# ArbPwrBoost_P6.net
KiCad netlist of a schematic drawn in Altium Designer
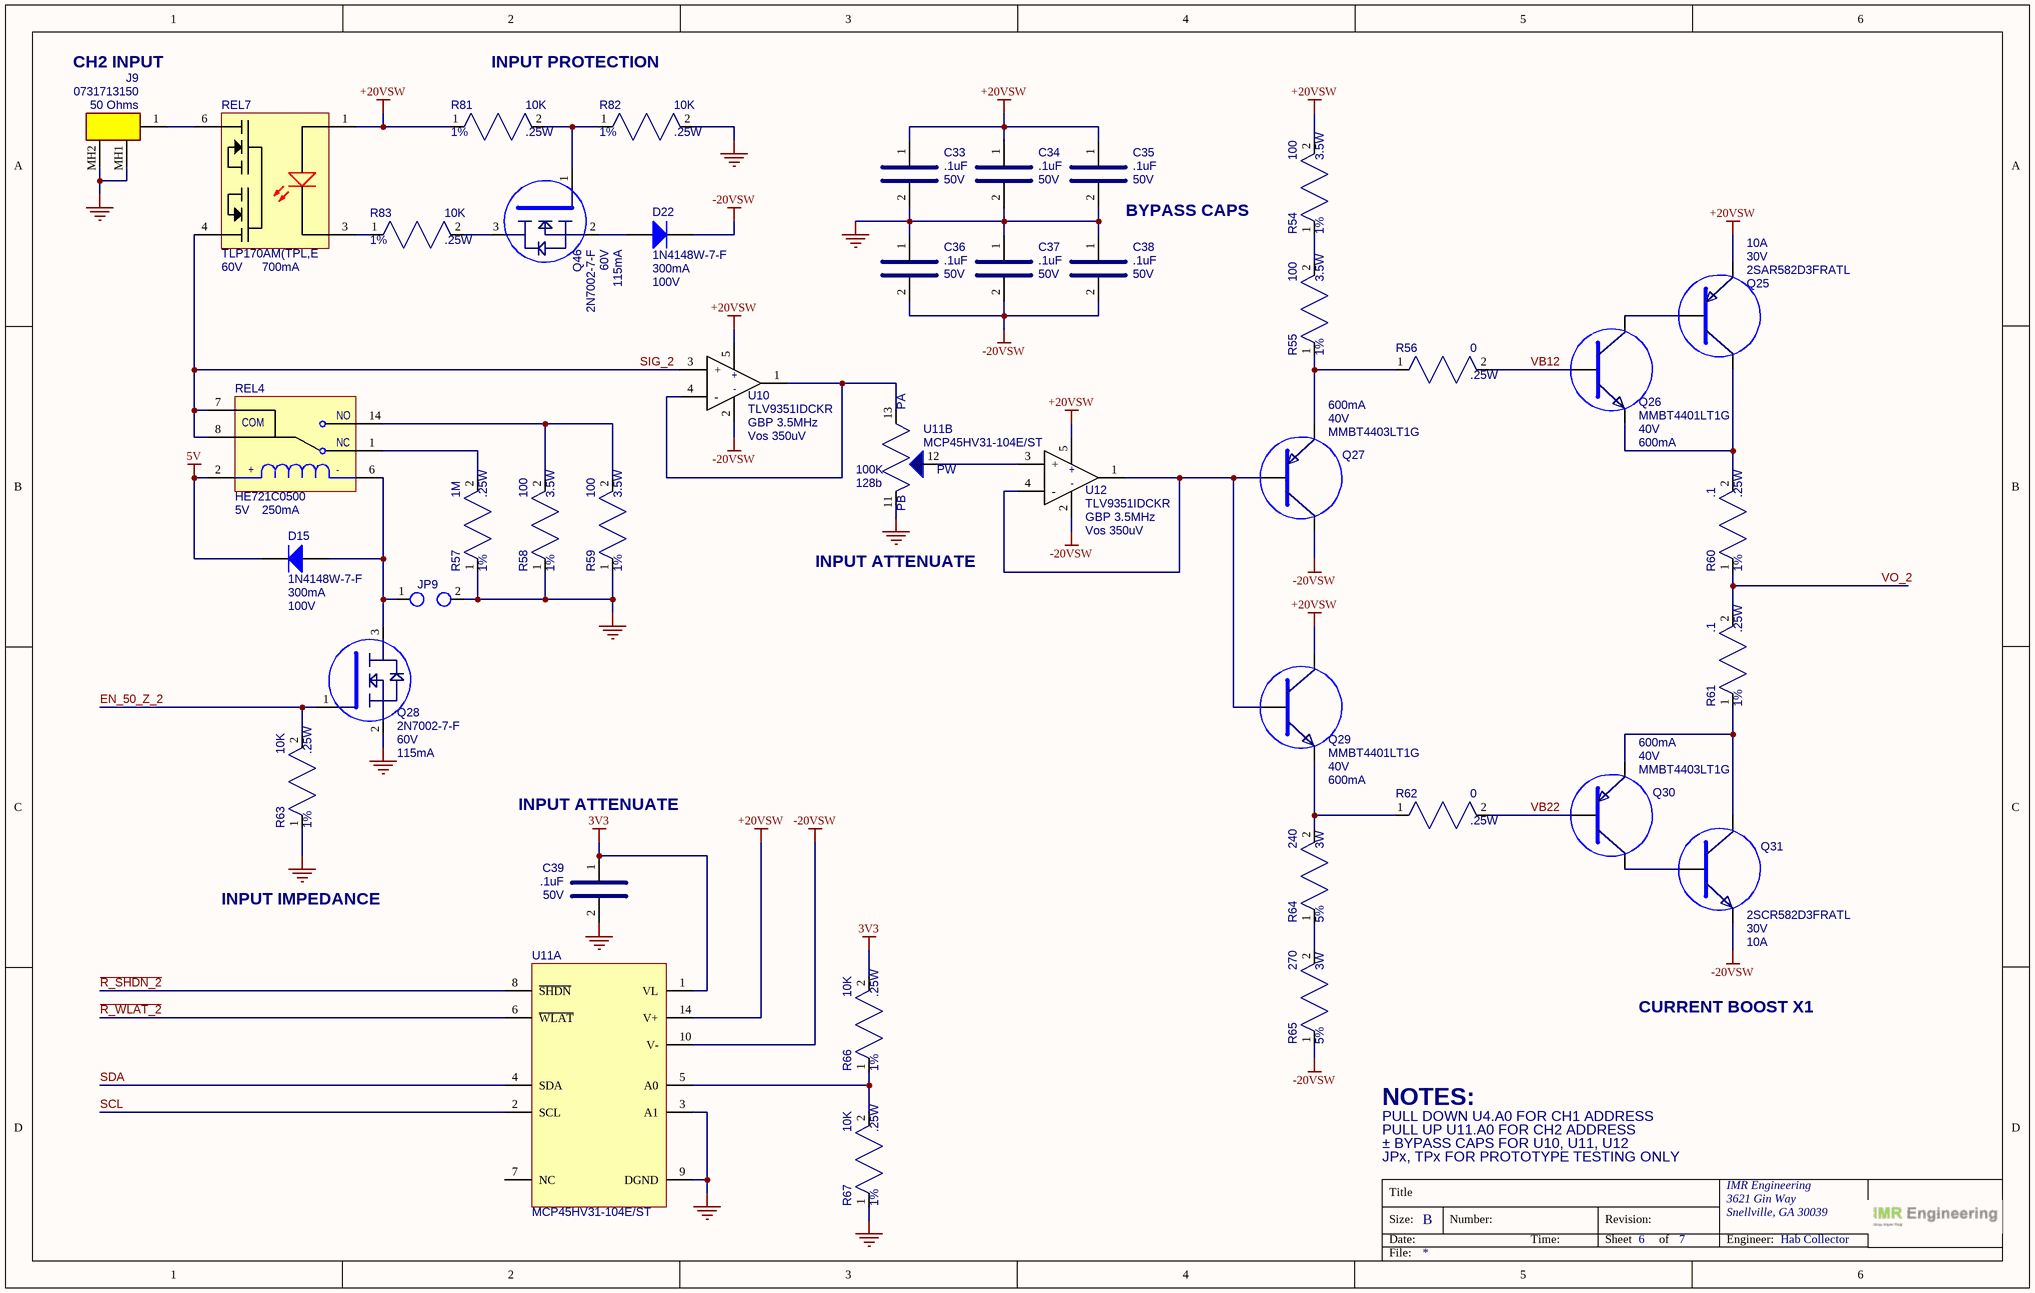
[diagram p0: ArbPwrBoost_P6.SchDoc]

(export (version "E")
  (design (tool "Eeschema 10.0.6"))
  (components
    (comp (ref "C33")
      (value ".1uF")
      (footprint "CAP_0805")
      (description "CAP CER 0.1UF 50V X7R 0805")
      (fields
        (field (name "MFG") "KYOCERA AVX")
        (field (name "VOLTAGE") "50V")
        (field (name "Comment") "KGM21NR71H104KT")
      )
      (libsource (lib "IMR_LIB_SCH_R2") (part "CAP_SMD_0.1UF_50V_0805"))
    )
    (comp (ref "C34")
      (value ".1uF")
      (footprint "CAP_0805")
      (description "CAP CER 0.1UF 50V X7R 0805")
      (fields
        (field (name "MFG") "KYOCERA AVX")
        (field (name "VOLTAGE") "50V")
        (field (name "Comment") "KGM21NR71H104KT")
      )
      (libsource (lib "IMR_LIB_SCH_R2") (part "CAP_SMD_0.1UF_50V_0805"))
    )
    (comp (ref "C35")
      (value ".1uF")
      (footprint "CAP_0805")
      (description "CAP CER 0.1UF 50V X7R 0805")
      (fields
        (field (name "MFG") "KYOCERA AVX")
        (field (name "VOLTAGE") "50V")
        (field (name "Comment") "KGM21NR71H104KT")
      )
      (libsource (lib "IMR_LIB_SCH_R2") (part "CAP_SMD_0.1UF_50V_0805"))
    )
    (comp (ref "C36")
      (value ".1uF")
      (footprint "CAP_0805")
      (description "CAP CER 0.1UF 50V X7R 0805")
      (fields
        (field (name "MFG") "KYOCERA AVX")
        (field (name "VOLTAGE") "50V")
        (field (name "Comment") "KGM21NR71H104KT")
      )
      (libsource (lib "IMR_LIB_SCH_R2") (part "CAP_SMD_0.1UF_50V_0805"))
    )
    (comp (ref "C37")
      (value ".1uF")
      (footprint "CAP_0805")
      (description "CAP CER 0.1UF 50V X7R 0805")
      (fields
        (field (name "MFG") "KYOCERA AVX")
        (field (name "VOLTAGE") "50V")
        (field (name "Comment") "KGM21NR71H104KT")
      )
      (libsource (lib "IMR_LIB_SCH_R2") (part "CAP_SMD_0.1UF_50V_0805"))
    )
    (comp (ref "C38")
      (value ".1uF")
      (footprint "CAP_0805")
      (description "CAP CER 0.1UF 50V X7R 0805")
      (fields
        (field (name "MFG") "KYOCERA AVX")
        (field (name "VOLTAGE") "50V")
        (field (name "Comment") "KGM21NR71H104KT")
      )
      (libsource (lib "IMR_LIB_SCH_R2") (part "CAP_SMD_0.1UF_50V_0805"))
    )
    (comp (ref "C39")
      (value ".1uF")
      (footprint "CAP_0805")
      (description "CAP CER 0.1UF 50V X7R 0805")
      (fields
        (field (name "MFG") "KYOCERA AVX")
        (field (name "VOLTAGE") "50V")
        (field (name "Comment") "KGM21NR71H104KT")
      )
      (libsource (lib "IMR_LIB_SCH_R2") (part "CAP_SMD_0.1UF_50V_0805"))
    )
    (comp (ref "D15")
      (value "100V")
      (footprint "SOD123")
      (description "RELAY REED SPDT 250MA 5V")
      (fields
        (field (name "MFG") "Diodes Inc")
        (field (name "MFG_PN") "1N4148W-7-F")
        (field (name "CURRENT") "300mA")
        (field (name "Comment") "1N4148W-7-F")
      )
      (libsource (lib "IMR_LIB_SCH_R2") (part "DIODE_1N4148W-7-F"))
    )
    (comp (ref "D22")
      (value "100V")
      (footprint "SOD123")
      (description "RELAY REED SPDT 250MA 5V")
      (fields
        (field (name "MFG") "Diodes Inc")
        (field (name "MFG_PN") "1N4148W-7-F")
        (field (name "CURRENT") "300mA")
        (field (name "Comment") "1N4148W-7-F")
      )
      (libsource (lib "IMR_LIB_SCH_R2") (part "DIODE_1N4148W-7-F"))
    )
    (comp (ref "J9")
      (value "50 Ohms")
      (footprint "731713150")
      (description "CONN BNC RCPT R/A 50 OHM PCB")
      (fields
        (field (name "MFG") "Molex")
        (field (name "MFG_PN") "0731713150")
        (field (name "Comment") "0731713150")
      )
      (libsource (lib "IMR_LIB_SCH_R2") (part "CONN_MOLEX_0731713150"))
    )
    (comp (ref "JP9")
      (value "PREC002SFAN-RC")
      (footprint "HDR_1X2_100MILL")
      (description "CONN HEADER VERT 2POS 2.54MM")
      (fields (field (name "MFG") "Sullins Connector Solutions"))
      (libsource (lib "IMR_LIB_SCH_R2") (part "CONN_JUMPER_2P_100MIL_VERT"))
    )
    (comp (ref "Q25")
      (value "30V")
      (footprint "TO-252")
      (description "TRANS PNP 30V 5.7A TO-252")
      (fields
        (field (name "MFG") "Rohm Semiconductor")
        (field (name "MFG_PN") "2SAR582D3FRATL")
        (field (name "CURRENT") "10A")
        (field (name "Comment") "2SAR582D3FRATL")
      )
      (libsource (lib "IMR_LIB_SCH_R2") (part "BJT_PNP_2SAR582D3FRATL"))
    )
    (comp (ref "Q26")
      (value "40V")
      (footprint "SOT-23")
      (description "TRANS NPN 40V 0.6A SOT23-3")
      (fields
        (field (name "MFG") "On Semiconductor")
        (field (name "MFG_PN") "MMBT4401LT1G")
        (field (name "CURRENT") "600mA")
        (field (name "Comment") "MMBT4401LT1G")
      )
      (libsource (lib "IMR_LIB_SCH_R2") (part "BJT_NPN_MMBT4401LT1G"))
    )
    (comp (ref "Q27")
      (value "40V")
      (footprint "SOT-23")
      (description "TRANS PNP 40V 0.6A SOT23-3")
      (fields
        (field (name "MFG") "On Semiconductor")
        (field (name "MFG_PN") "MMBT4403LT1G")
        (field (name "CURRENT") "600mA")
        (field (name "Comment") "MMBT4403LT1G")
      )
      (libsource (lib "IMR_LIB_SCH_R2") (part "BJT_PNP_MMBT4403LT1G"))
    )
    (comp (ref "Q28")
      (value "60V")
      (footprint "SOT-23")
      (description "MOSFET N-CH 60V 115MA SOT23-3")
      (fields
        (field (name "MFG") "Diodes Inc")
        (field (name "MFG_PN") "2N7002-7-F")
        (field (name "CURRENT") "115mA")
        (field (name "Comment") "2N7002-7-F")
      )
      (libsource (lib "") (part "MOSFET_NCH_2N7002-7-F_1"))
    )
    (comp (ref "Q29")
      (value "40V")
      (footprint "SOT-23")
      (description "TRANS NPN 40V 0.6A SOT23-3")
      (fields
        (field (name "MFG") "On Semiconductor")
        (field (name "MFG_PN") "MMBT4401LT1G")
        (field (name "CURRENT") "600mA")
        (field (name "Comment") "MMBT4401LT1G")
      )
      (libsource (lib "IMR_LIB_SCH_R2") (part "BJT_NPN_MMBT4401LT1G"))
    )
    (comp (ref "Q30")
      (value "40V")
      (footprint "SOT-23")
      (description "TRANS PNP 40V 0.6A SOT23-3")
      (fields
        (field (name "MFG") "On Semiconductor")
        (field (name "MFG_PN") "MMBT4403LT1G")
        (field (name "CURRENT") "600mA")
        (field (name "Comment") "MMBT4403LT1G")
      )
      (libsource (lib "IMR_LIB_SCH_R2") (part "BJT_PNP_MMBT4403LT1G"))
    )
    (comp (ref "Q31")
      (value "30V")
      (footprint "TO-252")
      (description "TRANS NPN 30V 10A TO-252")
      (fields
        (field (name "MFG") "Rohm Semiconductor")
        (field (name "MFG_PN") "2SCR582D3FRATL")
        (field (name "CURRENT") "10A")
        (field (name "Comment") "2SCR582D3FRATL")
      )
      (libsource (lib "IMR_LIB_SCH_R2") (part "BJT_NPN_2SCR582D3FRATL"))
    )
    (comp (ref "Q46")
      (value "60V")
      (footprint "SOT-23")
      (description "MOSFET N-CH 60V 115MA SOT23-3")
      (fields
        (field (name "MFG") "Diodes Inc")
        (field (name "MFG_PN") "2N7002-7-F")
        (field (name "CURRENT") "115mA")
        (field (name "Comment") "2N7002-7-F")
      )
      (libsource (lib "IMR_LIB_SCH_R2") (part "MOSFET_NCH_2N7002-7-F"))
    )
    (comp (ref "R54")
      (value "100")
      (footprint "RES_2512")
      (description "RES SMD 100 OHM 1% 3.5W 2512")
      (fields
        (field (name "MFG") "Ohmite")
        (field (name "POWER") "3.5W")
        (field (name "TOLERANCE") "1%")
        (field (name "Comment") "ALN2512F100RE-1")
      )
      (libsource (lib "IMR_LIB_SCH_R2") (part "RES_SMD_100_0805_3.5W_1%"))
    )
    (comp (ref "R55")
      (value "100")
      (footprint "RES_2512")
      (description "RES SMD 100 OHM 1% 3.5W 2512")
      (fields
        (field (name "MFG") "Ohmite")
        (field (name "POWER") "3.5W")
        (field (name "TOLERANCE") "1%")
        (field (name "Comment") "ALN2512F100RE-1")
      )
      (libsource (lib "IMR_LIB_SCH_R2") (part "RES_SMD_100_0805_3.5W_1%"))
    )
    (comp (ref "R56")
      (value "0")
      (footprint "RES_0805")
      (description "RES SMD 0 OHM 1% 1/8W 0805")
      (fields (field (name "MFG") "Yageo") (field (name "TOLERANCE") "1%") (field (name "POWER") ".25W"))
      (libsource (lib "IMR_LIB_SCH_R2") (part "RES_SMD_0_0805_1/8W_1%"))
    )
    (comp (ref "R57")
      (value "1M")
      (footprint "RES_0805")
      (description "RES SMD 1K OHM 1% 1/4W 0805")
      (fields
        (field (name "MFG") "Yageo")
        (field (name "POWER") ".25W")
        (field (name "TOLERANCE") "1%")
        (field (name "Comment") "RC0805FR-7W1ML")
      )
      (libsource (lib "IMR_LIB_SCH_R2") (part "RES_SMD_1M_0805_1/4W_1%"))
    )
    (comp (ref "R58")
      (value "100")
      (footprint "RES_2512")
      (description "RES SMD 100 OHM 1% 3.5W 2512")
      (fields
        (field (name "MFG") "Ohmite")
        (field (name "POWER") "3.5W")
        (field (name "TOLERANCE") "1%")
        (field (name "Comment") "ALN2512F100RE-1")
      )
      (libsource (lib "IMR_LIB_SCH_R2") (part "RES_SMD_100_0805_3.5W_1%"))
    )
    (comp (ref "R59")
      (value "100")
      (footprint "RES_2512")
      (description "RES SMD 100 OHM 1% 3.5W 2512")
      (fields
        (field (name "MFG") "Ohmite")
        (field (name "POWER") "3.5W")
        (field (name "TOLERANCE") "1%")
        (field (name "Comment") "ALN2512F100RE-1")
      )
      (libsource (lib "IMR_LIB_SCH_R2") (part "RES_SMD_100_0805_3.5W_1%"))
    )
    (comp (ref "R60")
      (value ".1")
      (footprint "RES_1206")
      (description "RES SMD 0.1 OHM 1% 1/4W 1206")
      (fields
        (field (name "MFG") "Yageo")
        (field (name "POWER") ".25W")
        (field (name "TOLERANCE") "1%")
        (field (name "Comment") "311-0.1LWCT-ND")
      )
      (libsource (lib "IMR_LIB_SCH_R2") (part "RES_SMD_0.1_1206_1/4W_1%"))
    )
    (comp (ref "R61")
      (value ".1")
      (footprint "RES_1206")
      (description "RES SMD 0.1 OHM 1% 1/4W 1206")
      (fields
        (field (name "MFG") "Yageo")
        (field (name "POWER") ".25W")
        (field (name "TOLERANCE") "1%")
        (field (name "Comment") "311-0.1LWCT-ND")
      )
      (libsource (lib "IMR_LIB_SCH_R2") (part "RES_SMD_0.1_1206_1/4W_1%"))
    )
    (comp (ref "R62")
      (value "0")
      (footprint "RES_0805")
      (description "RES SMD 0 OHM 1% 1/8W 0805")
      (fields (field (name "MFG") "Yageo") (field (name "TOLERANCE") "1%") (field (name "POWER") ".25W"))
      (libsource (lib "IMR_LIB_SCH_R2") (part "RES_SMD_0_0805_1/8W_1%"))
    )
    (comp (ref "R63")
      (value "10K")
      (footprint "RES_0805")
      (description "RES SMD 10K OHM 1% 1/4W 0805")
      (fields
        (field (name "MFG") "Yageo")
        (field (name "POWER") ".25W")
        (field (name "TOLERANCE") "1%")
        (field (name "Comment") "RC0805FR-7W10KL")
      )
      (libsource (lib "IMR_LIB_SCH_R2") (part "RES_SMD_10K_0805_1/4W_1%"))
    )
    (comp (ref "R64")
      (value "240")
      (footprint "RES_2512")
      (description "RES 240 OHM 5% 3W 2512")
      (fields
        (field (name "MFG") "Yageo")
        (field (name "POWER") "3W")
        (field (name "TOLERANCE") "5%")
        (field (name "Comment") "RC2512JK-07240RL")
      )
      (libsource (lib "IMR_LIB_SCH_R2") (part "RES_SMD_240_2512_3W_5%"))
    )
    (comp (ref "R65")
      (value "270")
      (footprint "RES_2512")
      (description "RES 270 OHM 5% 1W 2512")
      (fields
        (field (name "MFG") "Yageo")
        (field (name "POWER") "3W")
        (field (name "TOLERANCE") "5%")
        (field (name "Comment") "RC2512JK-07270RL")
      )
      (libsource (lib "IMR_LIB_SCH_R2") (part "RES_SMD_270_2512_3W_5%"))
    )
    (comp (ref "R66")
      (value "10K")
      (footprint "RES_0805")
      (description "RES SMD 10K OHM 1% 1/4W 0805")
      (fields
        (field (name "MFG") "Yageo")
        (field (name "POWER") ".25W")
        (field (name "TOLERANCE") "1%")
        (field (name "Comment") "RC0805FR-7W10KL")
      )
      (libsource (lib "IMR_LIB_SCH_R2") (part "RES_SMD_10K_0805_1/4W_1%"))
    )
    (comp (ref "R67")
      (value "10K")
      (footprint "RES_0805")
      (description "RES SMD 10K OHM 1% 1/4W 0805")
      (fields
        (field (name "MFG") "Yageo")
        (field (name "POWER") ".25W")
        (field (name "TOLERANCE") "1%")
        (field (name "Comment") "RC0805FR-7W10KL")
      )
      (libsource (lib "IMR_LIB_SCH_R2") (part "RES_SMD_10K_0805_1/4W_1%"))
    )
    (comp (ref "R81")
      (value "10K")
      (footprint "RES_0805")
      (description "RES SMD 10K OHM 1% 1/4W 0805")
      (fields
        (field (name "MFG") "Yageo")
        (field (name "POWER") ".25W")
        (field (name "TOLERANCE") "1%")
        (field (name "Comment") "RC0805FR-7W10KL")
      )
      (libsource (lib "IMR_LIB_SCH_R2") (part "RES_SMD_10K_0805_1/4W_1%"))
    )
    (comp (ref "R82")
      (value "10K")
      (footprint "RES_0805")
      (description "RES SMD 10K OHM 1% 1/4W 0805")
      (fields
        (field (name "MFG") "Yageo")
        (field (name "POWER") ".25W")
        (field (name "TOLERANCE") "1%")
        (field (name "Comment") "RC0805FR-7W10KL")
      )
      (libsource (lib "IMR_LIB_SCH_R2") (part "RES_SMD_10K_0805_1/4W_1%"))
    )
    (comp (ref "R83")
      (value "10K")
      (footprint "RES_0805")
      (description "RES SMD 10K OHM 1% 1/4W 0805")
      (fields
        (field (name "MFG") "Yageo")
        (field (name "POWER") ".25W")
        (field (name "TOLERANCE") "1%")
        (field (name "Comment") "RC0805FR-7W10KL")
      )
      (libsource (lib "IMR_LIB_SCH_R2") (part "RES_SMD_10K_0805_1/4W_1%"))
    )
    (comp (ref "REL4")
      (value "5V")
      (footprint "HE700")
      (description "RELAY REED SPDT 250MA 5V")
      (fields
        (field (name "MFG") "Littlefuse")
        (field (name "MFG_PN") "HE721C0500")
        (field (name "CURRENT") "250mA")
        (field (name "Comment") "HE721C0500")
      )
      (libsource (lib "IMR_LIB_SCH_R2") (part "RELAY_HE721C0500"))
    )
    (comp (ref "REL7")
      (value "60V")
      (footprint "SOP-6")
      (description "SSR RELAY SPST-NO 700MA 0-60V")
      (fields
        (field (name "MFG") "Toshiba")
        (field (name "MFG_PN") "TLP170AM(TPL,E")
        (field (name "CURRENT") "700mA")
        (field (name "Comment") "TLP170AM(TPL,E")
      )
      (libsource (lib "IMR_LIB_SCH_R2") (part "RELAY_TLP170AM(TPL,E"))
    )
    (comp (ref "U10")
      (value "GBP 3.5MHz")
      (footprint "SOT-353")
      (description "IC OPAMP GP 3.5MHZ 350uV C70-5")
      (fields
        (field (name "MFG") "Texas Instruments")
        (field (name "MFG_PN") "TLV9351IDCKR")
        (field (name "VOS") "Vos 350uV")
        (field (name "Comment") "TLV9351IDCKR")
      )
      (libsource (lib "IMR_LIB_SCH_R2") (part "OPAMP_TLV9351IDCKR"))
    )
    (comp (ref "U11")
      (value "100K")
      (footprint "TSSOP-14")
      (description "IC DGT POT 100KOHM 128TP 14TSSOP")
      (fields
        (field (name "MFG") "Microchip")
        (field (name "MFG_PN") "MCP45HV31-104E/ST")
        (field (name "TAP") "128b")
        (field (name "Comment") "MCP45HV31-104E/ST")
      )
      (libsource (lib "") (part "IC_MCP45HV31-104E/ST_1"))
    )
    (comp (ref "U12")
      (value "GBP 3.5MHz")
      (footprint "SOT-353")
      (description "IC OPAMP GP 3.5MHZ 350uV C70-5")
      (fields
        (field (name "MFG") "Texas Instruments")
        (field (name "MFG_PN") "TLV9351IDCKR")
        (field (name "VOS") "Vos 350uV")
        (field (name "Comment") "TLV9351IDCKR")
      )
      (libsource (lib "IMR_LIB_SCH_R2") (part "OPAMP_TLV9351IDCKR"))
    )
  )
  (nets
    (net (code "1") (name "+20VSW") (class "Default")
      (node (ref "C33") (pin "1") (pinfunction "1_1") (pintype "passive"))
      (node (ref "C34") (pin "1") (pinfunction "1_1") (pintype "passive"))
      (node (ref "C35") (pin "1") (pinfunction "1_1") (pintype "passive"))
      (node (ref "Q25") (pin "2") (pinfunction "E_2") (pintype "passive"))
      (node (ref "Q29") (pin "3") (pinfunction "C_3") (pintype "passive"))
      (node (ref "R54") (pin "2") (pinfunction "2_2") (pintype "passive"))
      (node (ref "R81") (pin "1") (pinfunction "1_1") (pintype "passive"))
      (node (ref "REL7") (pin "1") (pinfunction "1_1") (pintype "passive"))
      (node (ref "U10") (pin "5") (pintype "passive"))
      (node (ref "U11") (pin "14") (pinfunction "V+_14") (pintype "passive"))
      (node (ref "U12") (pin "5") (pintype "passive"))
    )
    (net (code "2") (name "-20VSW") (class "Default")
      (node (ref "C36") (pin "2") (pinfunction "2_2") (pintype "passive"))
      (node (ref "C37") (pin "2") (pinfunction "2_2") (pintype "passive"))
      (node (ref "C38") (pin "2") (pinfunction "2_2") (pintype "passive"))
      (node (ref "D22") (pin "2") (pinfunction "K_2") (pintype "passive"))
      (node (ref "Q27") (pin "3") (pinfunction "C_3") (pintype "passive"))
      (node (ref "Q31") (pin "2") (pinfunction "E_2") (pintype "passive"))
      (node (ref "R65") (pin "1") (pinfunction "1_1") (pintype "passive"))
      (node (ref "U10") (pin "2") (pintype "passive"))
      (node (ref "U11") (pin "10") (pinfunction "V-_10") (pintype "passive"))
      (node (ref "U12") (pin "2") (pintype "passive"))
    )
    (net (code "3") (name "/EN_50_Z_2") (class "Default")
      (node (ref "Q28") (pin "1") (pinfunction "B_1") (pintype "passive"))
      (node (ref "R63") (pin "2") (pinfunction "2_2") (pintype "passive"))
    )
    (net (code "4") (name "/SCL") (class "Default")
      (node (ref "U11") (pin "2") (pinfunction "SCL_2") (pintype "passive"))
    )
    (net (code "5") (name "/SDA") (class "Default")
      (node (ref "U11") (pin "4") (pinfunction "SDA_4") (pintype "passive"))
    )
    (net (code "6") (name "/SIG_2") (class "Default")
      (node (ref "REL4") (pin "7") (pinfunction "COM_7") (pintype "passive"))
      (node (ref "REL4") (pin "8") (pinfunction "COM_8") (pintype "passive"))
      (node (ref "REL7") (pin "4") (pinfunction "4_4") (pintype "passive"))
      (node (ref "U10") (pin "3") (pinfunction "+_3") (pintype "passive"))
    )
    (net (code "7") (name "/VB12") (class "Default")
      (node (ref "Q26") (pin "1") (pinfunction "B_1") (pintype "passive"))
      (node (ref "R56") (pin "2") (pinfunction "2_2") (pintype "passive"))
    )
    (net (code "8") (name "/VB22") (class "Default")
      (node (ref "Q30") (pin "1") (pinfunction "B_1") (pintype "passive"))
      (node (ref "R62") (pin "2") (pinfunction "2_2") (pintype "passive"))
    )
    (net (code "9") (name "/VO_2") (class "Default")
      (node (ref "R60") (pin "1") (pinfunction "1_1") (pintype "passive"))
      (node (ref "R61") (pin "2") (pinfunction "2_2") (pintype "passive"))
    )
    (net (code "10") (name "/~{R_SHDN_2}") (class "Default")
      (node (ref "U11") (pin "8") (pinfunction "~{SHDN}_8") (pintype "passive"))
    )
    (net (code "11") (name "/~{R_WLAT_2}") (class "Default")
      (node (ref "U11") (pin "6") (pinfunction "~{WLAT}_6") (pintype "passive"))
    )
    (net (code "12") (name "3V3") (class "Default")
      (node (ref "C39") (pin "1") (pinfunction "1_1") (pintype "passive"))
      (node (ref "R66") (pin "2") (pinfunction "2_2") (pintype "passive"))
      (node (ref "U11") (pin "1") (pinfunction "VL_1") (pintype "passive"))
    )
    (net (code "13") (name "5V") (class "Default")
      (node (ref "D15") (pin "2") (pinfunction "K_2") (pintype "passive"))
      (node (ref "REL4") (pin "2") (pintype "passive"))
    )
    (net (code "14") (name "GND") (class "Default")
      (node (ref "C33") (pin "2") (pinfunction "2_2") (pintype "passive"))
      (node (ref "C34") (pin "2") (pinfunction "2_2") (pintype "passive"))
      (node (ref "C35") (pin "2") (pinfunction "2_2") (pintype "passive"))
      (node (ref "C36") (pin "1") (pinfunction "1_1") (pintype "passive"))
      (node (ref "C37") (pin "1") (pinfunction "1_1") (pintype "passive"))
      (node (ref "C38") (pin "1") (pinfunction "1_1") (pintype "passive"))
      (node (ref "C39") (pin "2") (pinfunction "2_2") (pintype "passive"))
      (node (ref "J9") (pin "MH1") (pintype "passive"))
      (node (ref "J9") (pin "MH2") (pintype "passive"))
      (node (ref "JP9") (pin "2") (pintype "passive"))
      (node (ref "Q28") (pin "2") (pinfunction "E_2") (pintype "passive"))
      (node (ref "R57") (pin "1") (pinfunction "1_1") (pintype "passive"))
      (node (ref "R58") (pin "1") (pinfunction "1_1") (pintype "passive"))
      (node (ref "R59") (pin "1") (pinfunction "1_1") (pintype "passive"))
      (node (ref "R63") (pin "1") (pinfunction "1_1") (pintype "passive"))
      (node (ref "R67") (pin "1") (pinfunction "1_1") (pintype "passive"))
      (node (ref "R82") (pin "2") (pinfunction "2_2") (pintype "passive"))
      (node (ref "U11") (pin "11") (pinfunction "PB0_11") (pintype "passive"))
      (node (ref "U11") (pin "3") (pinfunction "A1_3") (pintype "passive"))
      (node (ref "U11") (pin "9") (pinfunction "DGND_9") (pintype "passive"))
    )
    (net (code "15") (name "Net-(D15-A)") (class "Default")
      (node (ref "D15") (pin "1") (pinfunction "A_1") (pintype "passive"))
      (node (ref "JP9") (pin "1") (pintype "passive"))
      (node (ref "Q28") (pin "3") (pinfunction "C_3") (pintype "passive"))
      (node (ref "REL4") (pin "6") (pintype "passive"))
    )
    (net (code "16") (name "Net-(D22-A)") (class "Default")
      (node (ref "D22") (pin "1") (pinfunction "A_1") (pintype "passive"))
      (node (ref "Q46") (pin "2") (pinfunction "E_2") (pintype "passive"))
    )
    (net (code "17") (name "Net-(J9-Pad1)") (class "Default")
      (node (ref "J9") (pin "1") (pintype "passive"))
      (node (ref "REL7") (pin "6") (pinfunction "6_6") (pintype "passive"))
    )
    (net (code "18") (name "Net-(Q25-B)") (class "Default")
      (node (ref "Q25") (pin "1") (pinfunction "B_1") (pintype "passive"))
      (node (ref "Q26") (pin "3") (pinfunction "C_3") (pintype "passive"))
    )
    (net (code "19") (name "Net-(Q25-C)") (class "Default")
      (node (ref "Q25") (pin "3") (pinfunction "C_3") (pintype "passive"))
      (node (ref "Q26") (pin "2") (pinfunction "E_2") (pintype "passive"))
      (node (ref "R60") (pin "2") (pinfunction "2_2") (pintype "passive"))
    )
    (net (code "20") (name "Net-(Q27-B)") (class "Default")
      (node (ref "Q27") (pin "1") (pinfunction "B_1") (pintype "passive"))
      (node (ref "Q29") (pin "1") (pinfunction "B_1") (pintype "passive"))
      (node (ref "U12") (pin "1") (pintype "passive"))
      (node (ref "U12") (pin "4") (pinfunction "-_4") (pintype "passive"))
    )
    (net (code "21") (name "Net-(Q27-E)") (class "Default")
      (node (ref "Q27") (pin "2") (pinfunction "E_2") (pintype "passive"))
      (node (ref "R55") (pin "1") (pinfunction "1_1") (pintype "passive"))
      (node (ref "R56") (pin "1") (pinfunction "1_1") (pintype "passive"))
    )
    (net (code "22") (name "Net-(Q29-E)") (class "Default")
      (node (ref "Q29") (pin "2") (pinfunction "E_2") (pintype "passive"))
      (node (ref "R62") (pin "1") (pinfunction "1_1") (pintype "passive"))
      (node (ref "R64") (pin "2") (pinfunction "2_2") (pintype "passive"))
    )
    (net (code "23") (name "Net-(Q30-C)") (class "Default")
      (node (ref "Q30") (pin "3") (pinfunction "C_3") (pintype "passive"))
      (node (ref "Q31") (pin "1") (pinfunction "B_1") (pintype "passive"))
    )
    (net (code "24") (name "Net-(Q30-E)") (class "Default")
      (node (ref "Q30") (pin "2") (pinfunction "E_2") (pintype "passive"))
      (node (ref "Q31") (pin "3") (pinfunction "C_3") (pintype "passive"))
      (node (ref "R61") (pin "1") (pinfunction "1_1") (pintype "passive"))
    )
    (net (code "25") (name "Net-(Q46-B)") (class "Default")
      (node (ref "Q46") (pin "1") (pinfunction "B_1") (pintype "passive"))
      (node (ref "R81") (pin "2") (pinfunction "2_2") (pintype "passive"))
      (node (ref "R82") (pin "1") (pinfunction "1_1") (pintype "passive"))
    )
    (net (code "26") (name "Net-(Q46-C)") (class "Default")
      (node (ref "Q46") (pin "3") (pinfunction "C_3") (pintype "passive"))
      (node (ref "R83") (pin "2") (pinfunction "2_2") (pintype "passive"))
    )
    (net (code "27") (name "Net-(R54-Pad1)") (class "Default")
      (node (ref "R54") (pin "1") (pinfunction "1_1") (pintype "passive"))
      (node (ref "R55") (pin "2") (pinfunction "2_2") (pintype "passive"))
    )
    (net (code "28") (name "Net-(R64-Pad1)") (class "Default")
      (node (ref "R64") (pin "1") (pinfunction "1_1") (pintype "passive"))
      (node (ref "R65") (pin "2") (pinfunction "2_2") (pintype "passive"))
    )
    (net (code "29") (name "Net-(R83-Pad1)") (class "Default")
      (node (ref "R83") (pin "1") (pinfunction "1_1") (pintype "passive"))
      (node (ref "REL7") (pin "3") (pinfunction "3_3") (pintype "passive"))
    )
    (net (code "30") (name "Net-(REL4-NC)") (class "Default")
      (node (ref "R57") (pin "2") (pinfunction "2_2") (pintype "passive"))
      (node (ref "REL4") (pin "1") (pinfunction "NC_1") (pintype "passive"))
    )
    (net (code "31") (name "Net-(REL4-NO)") (class "Default")
      (node (ref "R58") (pin "2") (pinfunction "2_2") (pintype "passive"))
      (node (ref "R59") (pin "2") (pinfunction "2_2") (pintype "passive"))
      (node (ref "REL4") (pin "14") (pinfunction "NO_14") (pintype "passive"))
    )
    (net (code "32") (name "Net-(U10--)") (class "Default")
      (node (ref "U10") (pin "1") (pintype "passive"))
      (node (ref "U10") (pin "4") (pinfunction "-_4") (pintype "passive"))
      (node (ref "U11") (pin "13") (pinfunction "PA_13") (pintype "passive"))
    )
    (net (code "33") (name "Net-(U11A-A0)") (class "Default")
      (node (ref "R66") (pin "1") (pinfunction "1_1") (pintype "passive"))
      (node (ref "R67") (pin "2") (pinfunction "2_2") (pintype "passive"))
      (node (ref "U11") (pin "5") (pinfunction "A0_5") (pintype "passive"))
    )
    (net (code "34") (name "Net-(U11B-PW0)") (class "Default")
      (node (ref "U11") (pin "12") (pinfunction "PW0_12") (pintype "passive"))
      (node (ref "U12") (pin "3") (pinfunction "+_3") (pintype "passive"))
    )
    (net (code "35") (name "unconnected-(U11A-NC-Pad7)") (class "Default")
      (node (ref "U11") (pin "7") (pinfunction "NC_7") (pintype "passive"))
    )
  )
)
